# controller.net
KiCad netlist of a schematic drawn in EAGLE
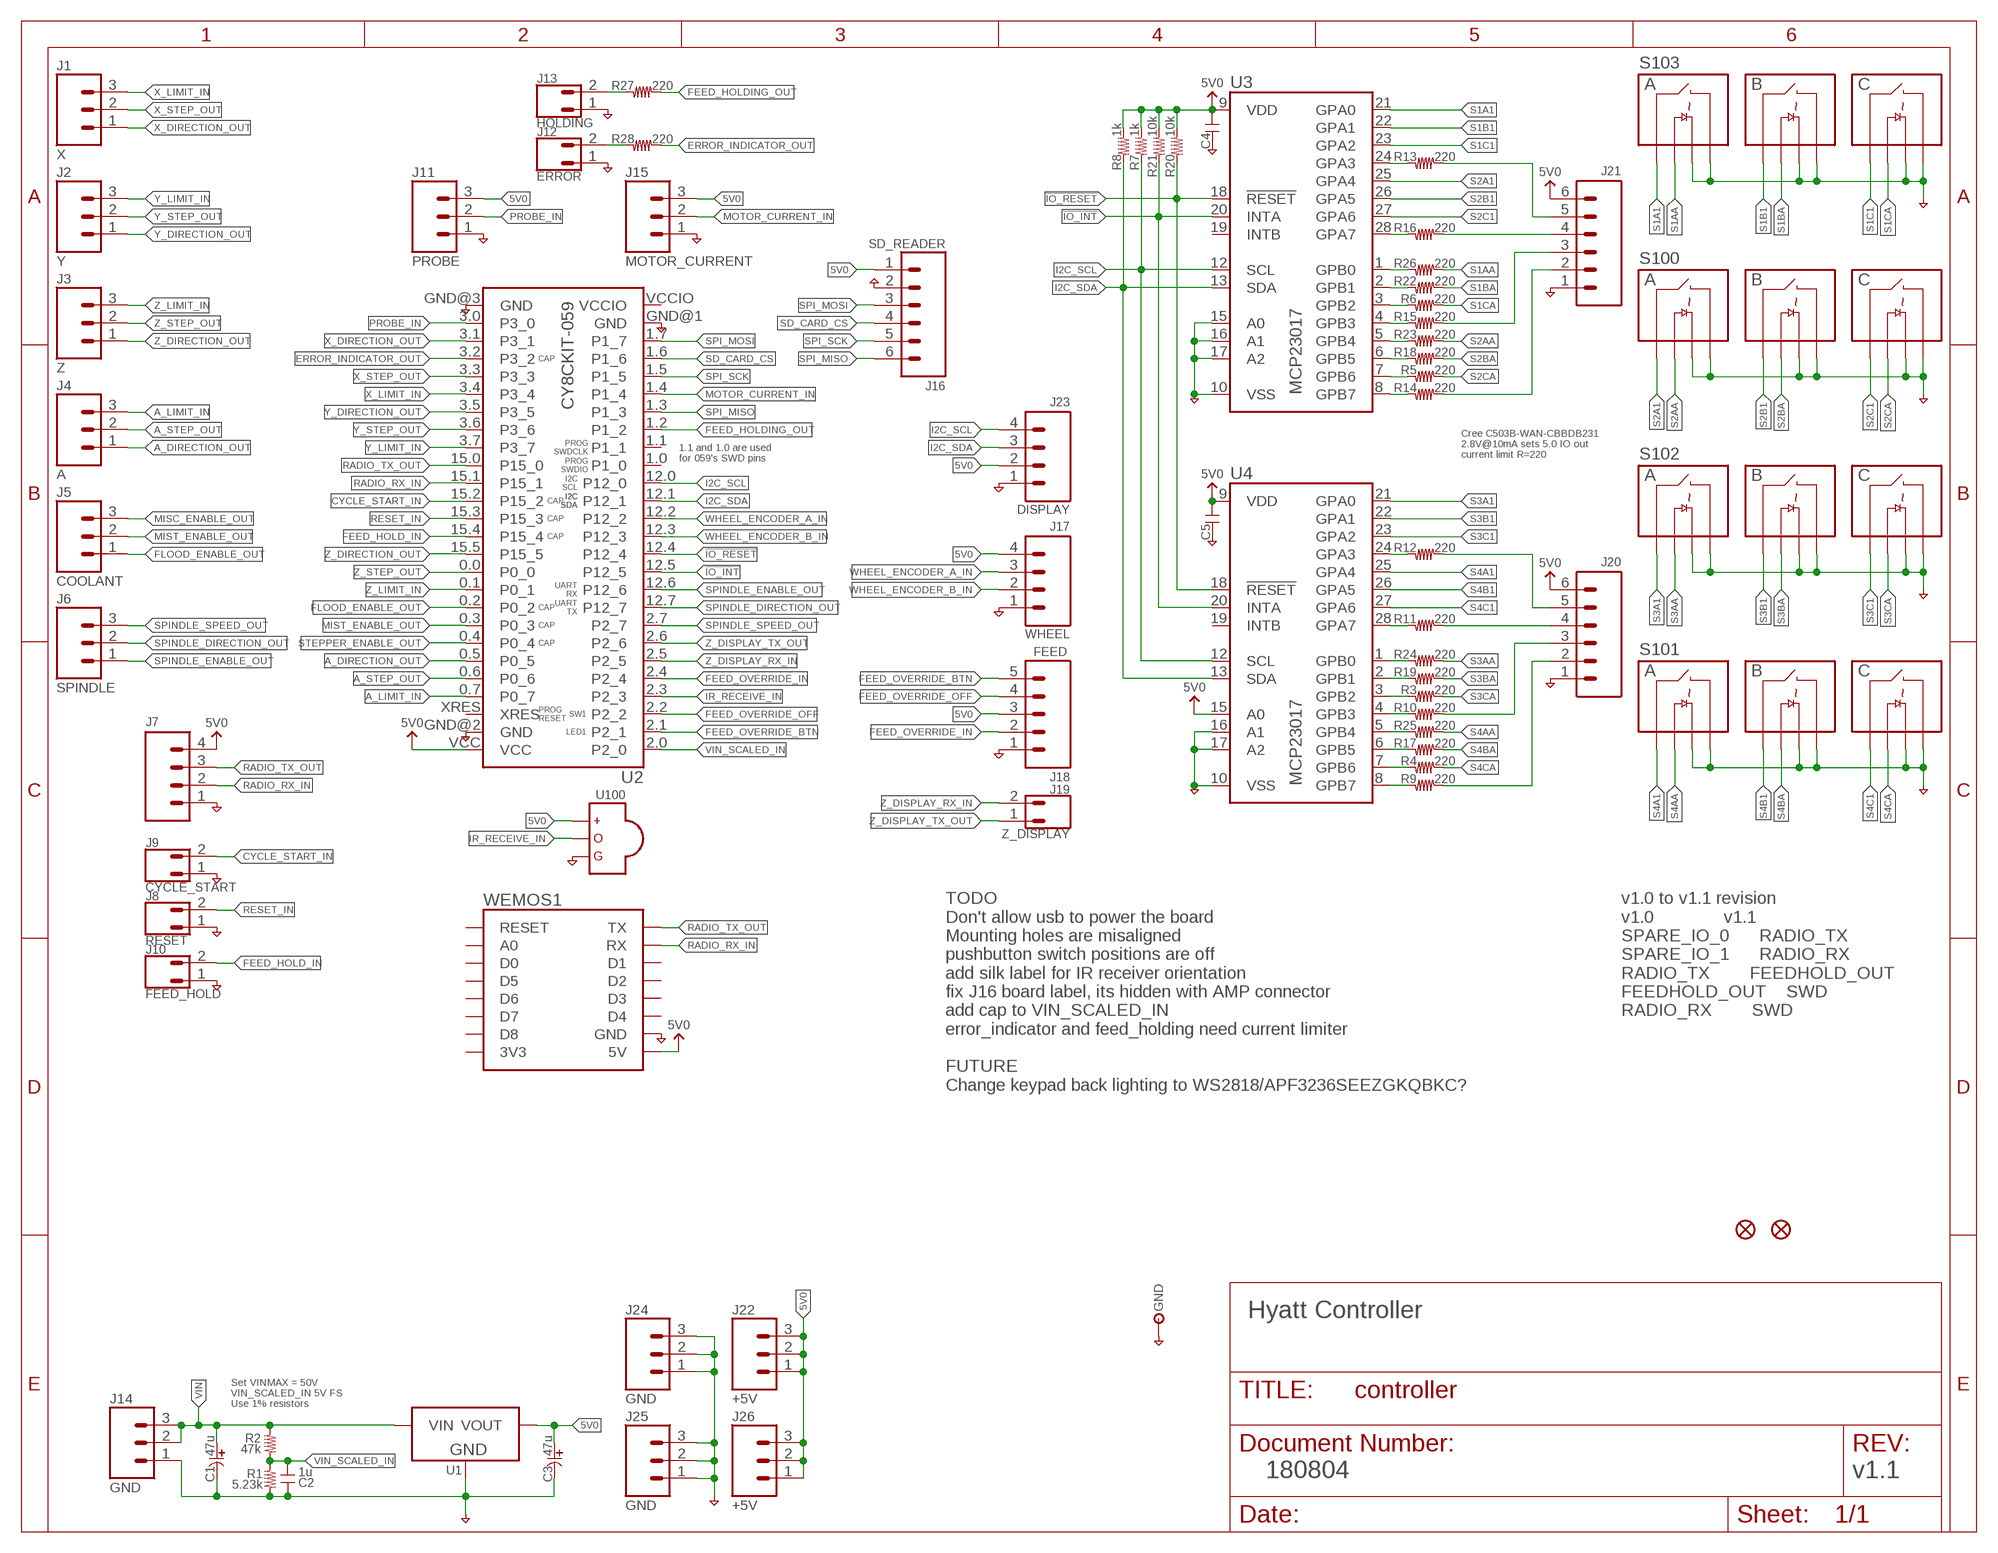
[diagram p0: schematic, sheet 1]

(export (version "E")
  (design (tool "Eeschema 10.0.6"))
  (components
    (comp (ref "C1")
      (value "47u")
      (footprint "eagle-import:E5-10")
      (libsource (lib "eagle-import") (part "C-POLARIZED-E5-10"))
    )
    (comp (ref "C2")
      (value "1u")
      (footprint "eagle-import:C0603")
      (libsource (lib "eagle-import") (part "C-0603"))
    )
    (comp (ref "C3")
      (value "47u")
      (footprint "eagle-import:E5-10")
      (libsource (lib "eagle-import") (part "C-POLARIZED-E5-10"))
    )
    (comp (ref "C4")
      (value "C-0603")
      (footprint "eagle-import:C0603")
      (libsource (lib "eagle-import") (part "C-0603"))
    )
    (comp (ref "C5")
      (value "C-0603")
      (footprint "eagle-import:C0603")
      (libsource (lib "eagle-import") (part "C-0603"))
    )
    (comp (ref "FID1")
      (value "FIDUCIAL1.5X3")
      (footprint "eagle-import:FIDUCIAL-1.5X3")
      (libsource (lib "eagle-import") (part "FIDUCIAL1.5X3"))
    )
    (comp (ref "FID2")
      (value "FIDUCIAL1.5X3")
      (footprint "eagle-import:FIDUCIAL-1.5X3")
      (libsource (lib "eagle-import") (part "FIDUCIAL1.5X3"))
    )
    (comp (ref "GND")
      (value "TESTPOINTTHRU")
      (footprint "eagle-import:TPTHRU")
      (libsource (lib "eagle-import") (part "TESTPOINTTHRU"))
    )
    (comp (ref "J1")
      (value "X")
      (footprint "eagle-import:CONN-3.81MM-KF2EDG-3")
      (libsource (lib "eagle-import") (part "CONN-03-3.81MM-PLUGIN-SCREW"))
    )
    (comp (ref "J2")
      (value "Y")
      (footprint "eagle-import:CONN-3.81MM-KF2EDG-3")
      (libsource (lib "eagle-import") (part "CONN-03-3.81MM-PLUGIN-SCREW"))
    )
    (comp (ref "J3")
      (value "Z")
      (footprint "eagle-import:CONN-3.81MM-KF2EDG-3")
      (libsource (lib "eagle-import") (part "CONN-03-3.81MM-PLUGIN-SCREW"))
    )
    (comp (ref "J4")
      (value "A")
      (footprint "eagle-import:CONN-3.81MM-KF2EDG-3")
      (libsource (lib "eagle-import") (part "CONN-03-3.81MM-PLUGIN-SCREW"))
    )
    (comp (ref "J5")
      (value "COOLANT")
      (footprint "eagle-import:CONN-3.81MM-KF2EDG-3")
      (libsource (lib "eagle-import") (part "CONN-03-3.81MM-PLUGIN-SCREW"))
    )
    (comp (ref "J6")
      (value "SPINDLE")
      (footprint "eagle-import:CONN-3.81MM-KF2EDG-3")
      (libsource (lib "eagle-import") (part "CONN-03-3.81MM-PLUGIN-SCREW"))
    )
    (comp (ref "J7")
      (value "CONN-04-0.1")
      (footprint "eagle-import:1X04")
      (libsource (lib "eagle-import") (part "CONN-04-0.1"))
    )
    (comp (ref "J8")
      (value "RESET")
      (footprint "eagle-import:CONN-.100-2")
      (libsource (lib "eagle-import") (part "CONN-02-.100-VERT-HEADER"))
    )
    (comp (ref "J9")
      (value "CYCLE_START")
      (footprint "eagle-import:CONN-.100-2")
      (libsource (lib "eagle-import") (part "CONN-02-.100-VERT-HEADER"))
    )
    (comp (ref "J10")
      (value "FEED_HOLD")
      (footprint "eagle-import:CONN-.100-2")
      (libsource (lib "eagle-import") (part "CONN-02-.100-VERT-HEADER"))
    )
    (comp (ref "J11")
      (value "PROBE")
      (footprint "eagle-import:CONN-3.81MM-KF2EDG-3")
      (libsource (lib "eagle-import") (part "CONN-03-3.81MM-PLUGIN-SCREW"))
    )
    (comp (ref "J12")
      (value "ERROR")
      (footprint "eagle-import:CONN-.100-2")
      (libsource (lib "eagle-import") (part "CONN-02-.100-VERT-HEADER"))
    )
    (comp (ref "J13")
      (value "HOLDING")
      (footprint "eagle-import:CONN-.100-2")
      (libsource (lib "eagle-import") (part "CONN-02-.100-VERT-HEADER"))
    )
    (comp (ref "J14")
      (value "GND")
      (footprint "eagle-import:CONN-3.81MM-KF2EDG-3")
      (libsource (lib "eagle-import") (part "CONN-03-3.81MM-PLUGIN-SCREW"))
    )
    (comp (ref "J15")
      (value "MOTOR_CURRENT")
      (footprint "eagle-import:CONN-3.81MM-KF2EDG-3")
      (libsource (lib "eagle-import") (part "CONN-03-3.81MM-PLUGIN-SCREW"))
    )
    (comp (ref "J16")
      (value "SD_READER")
      (footprint "eagle-import:1X06")
      (libsource (lib "eagle-import") (part "CONN-06-0.1"))
    )
    (comp (ref "J17")
      (value "WHEEL")
      (footprint "eagle-import:CONN-.100-4")
      (libsource (lib "eagle-import") (part "CONN-04-.100-VERT-HEADER"))
    )
    (comp (ref "J18")
      (value "FEED")
      (footprint "eagle-import:1X05")
      (libsource (lib "eagle-import") (part "CONN-05-PTH"))
    )
    (comp (ref "J19")
      (value "Z_DISPLAY")
      (footprint "eagle-import:CONN-3.81MM-KF2EDG-2")
      (libsource (lib "eagle-import") (part "CONN-02-3.81MM-PLUGIN-SCREW"))
    )
    (comp (ref "J20")
      (value "CONN-06-.100-VERT-HEADER")
      (footprint "eagle-import:CONN-.100-6")
      (libsource (lib "eagle-import") (part "CONN-06-.100-VERT-HEADER"))
    )
    (comp (ref "J21")
      (value "CONN-06-.100-VERT-HEADER")
      (footprint "eagle-import:CONN-.100-6")
      (libsource (lib "eagle-import") (part "CONN-06-.100-VERT-HEADER"))
    )
    (comp (ref "J22")
      (value "+5V")
      (footprint "eagle-import:CONN-3.81MM-KF2EDG-3")
      (libsource (lib "eagle-import") (part "CONN-03-3.81MM-PLUGIN-SCREW"))
    )
    (comp (ref "J23")
      (value "DISPLAY")
      (footprint "eagle-import:CONN-.100-4")
      (libsource (lib "eagle-import") (part "CONN-04-.100-VERT-HEADER"))
    )
    (comp (ref "J24")
      (value "GND")
      (footprint "eagle-import:CONN-3.81MM-KF2EDG-3")
      (libsource (lib "eagle-import") (part "CONN-03-3.81MM-PLUGIN-SCREW"))
    )
    (comp (ref "J25")
      (value "GND")
      (footprint "eagle-import:CONN-3.81MM-KF2EDG-3")
      (libsource (lib "eagle-import") (part "CONN-03-3.81MM-PLUGIN-SCREW"))
    )
    (comp (ref "J26")
      (value "+5V")
      (footprint "eagle-import:CONN-3.81MM-KF2EDG-3")
      (libsource (lib "eagle-import") (part "CONN-03-3.81MM-PLUGIN-SCREW"))
    )
    (comp (ref "R1")
      (value "5.23k")
      (footprint "eagle-import:R0603")
      (libsource (lib "eagle-import") (part "R-0603"))
    )
    (comp (ref "R2")
      (value "47k")
      (footprint "eagle-import:R0603")
      (libsource (lib "eagle-import") (part "R-0603"))
    )
    (comp (ref "R3")
      (value "220")
      (footprint "eagle-import:R0603")
      (libsource (lib "eagle-import") (part "R-0603"))
    )
    (comp (ref "R4")
      (value "220")
      (footprint "eagle-import:R0603")
      (libsource (lib "eagle-import") (part "R-0603"))
    )
    (comp (ref "R5")
      (value "220")
      (footprint "eagle-import:R0603")
      (libsource (lib "eagle-import") (part "R-0603"))
    )
    (comp (ref "R6")
      (value "220")
      (footprint "eagle-import:R0603")
      (libsource (lib "eagle-import") (part "R-0603"))
    )
    (comp (ref "R7")
      (value "1k")
      (footprint "eagle-import:R0603")
      (libsource (lib "eagle-import") (part "R-0603"))
    )
    (comp (ref "R8")
      (value "1k")
      (footprint "eagle-import:R0603")
      (libsource (lib "eagle-import") (part "R-0603"))
    )
    (comp (ref "R9")
      (value "220")
      (footprint "eagle-import:R0603")
      (libsource (lib "eagle-import") (part "R-0603"))
    )
    (comp (ref "R10")
      (value "220")
      (footprint "eagle-import:R0603")
      (libsource (lib "eagle-import") (part "R-0603"))
    )
    (comp (ref "R11")
      (value "220")
      (footprint "eagle-import:R0603")
      (libsource (lib "eagle-import") (part "R-0603"))
    )
    (comp (ref "R12")
      (value "220")
      (footprint "eagle-import:R0603")
      (libsource (lib "eagle-import") (part "R-0603"))
    )
    (comp (ref "R13")
      (value "220")
      (footprint "eagle-import:R0603")
      (libsource (lib "eagle-import") (part "R-0603"))
    )
    (comp (ref "R14")
      (value "220")
      (footprint "eagle-import:R0603")
      (libsource (lib "eagle-import") (part "R-0603"))
    )
    (comp (ref "R15")
      (value "220")
      (footprint "eagle-import:R0603")
      (libsource (lib "eagle-import") (part "R-0603"))
    )
    (comp (ref "R16")
      (value "220")
      (footprint "eagle-import:R0603")
      (libsource (lib "eagle-import") (part "R-0603"))
    )
    (comp (ref "R17")
      (value "220")
      (footprint "eagle-import:R0603")
      (libsource (lib "eagle-import") (part "R-0603"))
    )
    (comp (ref "R18")
      (value "220")
      (footprint "eagle-import:R0603")
      (libsource (lib "eagle-import") (part "R-0603"))
    )
    (comp (ref "R19")
      (value "220")
      (footprint "eagle-import:R0603")
      (libsource (lib "eagle-import") (part "R-0603"))
    )
    (comp (ref "R20")
      (value "10k")
      (footprint "eagle-import:R0603")
      (libsource (lib "eagle-import") (part "R-0603"))
    )
    (comp (ref "R21")
      (value "10k")
      (footprint "eagle-import:R0603")
      (libsource (lib "eagle-import") (part "R-0603"))
    )
    (comp (ref "R22")
      (value "220")
      (footprint "eagle-import:R0603")
      (libsource (lib "eagle-import") (part "R-0603"))
    )
    (comp (ref "R23")
      (value "220")
      (footprint "eagle-import:R0603")
      (libsource (lib "eagle-import") (part "R-0603"))
    )
    (comp (ref "R24")
      (value "220")
      (footprint "eagle-import:R0603")
      (libsource (lib "eagle-import") (part "R-0603"))
    )
    (comp (ref "R25")
      (value "220")
      (footprint "eagle-import:R0603")
      (libsource (lib "eagle-import") (part "R-0603"))
    )
    (comp (ref "R26")
      (value "220")
      (footprint "eagle-import:R0603")
      (libsource (lib "eagle-import") (part "R-0603"))
    )
    (comp (ref "R27")
      (value "220")
      (footprint "eagle-import:R0603")
      (libsource (lib "eagle-import") (part "R-0603"))
    )
    (comp (ref "R28")
      (value "220")
      (footprint "eagle-import:R0603")
      (libsource (lib "eagle-import") (part "R-0603"))
    )
    (comp (ref "S100")
      (value "SWITCH-DTMF-3-LED")
      (footprint "eagle-import:SWITCH-DTMF-3-LED")
      (libsource (lib "eagle-import") (part "SWITCH-DTMF-3-LED"))
    )
    (comp (ref "S101")
      (value "SWITCH-DTMF-3-LED")
      (footprint "eagle-import:SWITCH-DTMF-3-LED")
      (libsource (lib "eagle-import") (part "SWITCH-DTMF-3-LED"))
    )
    (comp (ref "S102")
      (value "SWITCH-DTMF-3-LED")
      (footprint "eagle-import:SWITCH-DTMF-3-LED")
      (libsource (lib "eagle-import") (part "SWITCH-DTMF-3-LED"))
    )
    (comp (ref "S103")
      (value "SWITCH-DTMF-3-LED")
      (footprint "eagle-import:SWITCH-DTMF-3-LED")
      (libsource (lib "eagle-import") (part "SWITCH-DTMF-3-LED"))
    )
    (comp (ref "U1")
      (value "VREG-SIP3")
      (footprint "eagle-import:VREG-SIP3")
      (libsource (lib "eagle-import") (part "VREG-SIP3"))
    )
    (comp (ref "U2")
      (value "BOARD-PSOC-CY8CKIT-059")
      (footprint "eagle-import:BOARD-PSOC-CY8CKIT-059")
      (libsource (lib "eagle-import") (part "BOARD-PSOC-CY8CKIT-059"))
    )
    (comp (ref "U3")
      (value "MCP23017")
      (footprint "eagle-import:SO28W")
      (fields (field (name "MF") "MICROCHIP") (field (name "MPN") "MCP23017-E/SO"))
      (libsource (lib "eagle-import") (part "IO-MCP23017SO"))
    )
    (comp (ref "U4")
      (value "MCP23017")
      (footprint "eagle-import:SO28W")
      (fields (field (name "MF") "MICROCHIP") (field (name "MPN") "MCP23017-E/SO"))
      (libsource (lib "eagle-import") (part "IO-MCP23017SO"))
    )
    (comp (ref "U100")
      (value "SENSOR-IR-THRU")
      (footprint "eagle-import:IRDETECTOR-THRU")
      (libsource (lib "eagle-import") (part "SENSOR-IR-THRU"))
    )
    (comp (ref "WEMOS1")
      (value "RADIO-WEMOS-D1-MINI")
      (footprint "eagle-import:WEMOS-D1-MINI")
      (libsource (lib "eagle-import") (part "RADIO-WEMOS-D1-MINI"))
    )
  )
  (nets
    (net (code "1") (name "/~{IO_INT}") (class "Default")
      (node (ref "R21") (pin "1") (pinfunction "1_1") (pintype "passive"))
      (node (ref "U2") (pin "12.5") (pinfunction "P12_5_12.5") (pintype "bidirectional"))
      (node (ref "U3") (pin "20") (pinfunction "INTA_20") (pintype "output"))
      (node (ref "U4") (pin "20") (pinfunction "INTA_20") (pintype "output"))
    )
    (net (code "2") (name "/~{IO_RESET}") (class "Default")
      (node (ref "R20") (pin "1") (pinfunction "1_1") (pintype "passive"))
      (node (ref "U2") (pin "12.4") (pinfunction "P12_4_12.4") (pintype "bidirectional"))
      (node (ref "U3") (pin "18") (pinfunction "~{RESET}_18") (pintype "input"))
      (node (ref "U4") (pin "18") (pinfunction "~{RESET}_18") (pintype "input"))
    )
    (net (code "3") (name "5V0") (class "Default")
      (node (ref "C3") (pin "+") (pinfunction "+_+") (pintype "passive"))
      (node (ref "C4") (pin "1") (pinfunction "1_1") (pintype "passive"))
      (node (ref "C5") (pin "1") (pinfunction "1_1") (pintype "passive"))
      (node (ref "J11") (pin "3") (pinfunction "3_3") (pintype "passive"))
      (node (ref "J15") (pin "3") (pinfunction "3_3") (pintype "passive"))
      (node (ref "J16") (pin "1") (pinfunction "1_1") (pintype "passive"))
      (node (ref "J17") (pin "4") (pinfunction "4_4") (pintype "passive"))
      (node (ref "J18") (pin "3") (pinfunction "3_3") (pintype "passive"))
      (node (ref "J20") (pin "6") (pinfunction "6_6") (pintype "passive"))
      (node (ref "J21") (pin "6") (pinfunction "6_6") (pintype "passive"))
      (node (ref "J22") (pin "1") (pinfunction "1_1") (pintype "passive"))
      (node (ref "J22") (pin "2") (pinfunction "2_2") (pintype "passive"))
      (node (ref "J22") (pin "3") (pinfunction "3_3") (pintype "passive"))
      (node (ref "J23") (pin "2") (pinfunction "2_2") (pintype "passive"))
      (node (ref "J26") (pin "1") (pinfunction "1_1") (pintype "passive"))
      (node (ref "J26") (pin "2") (pinfunction "2_2") (pintype "passive"))
      (node (ref "J26") (pin "3") (pinfunction "3_3") (pintype "passive"))
      (node (ref "J7") (pin "4") (pinfunction "4_4") (pintype "passive"))
      (node (ref "R20") (pin "2") (pinfunction "2_2") (pintype "passive"))
      (node (ref "R21") (pin "2") (pinfunction "2_2") (pintype "passive"))
      (node (ref "R7") (pin "2") (pinfunction "2_2") (pintype "passive"))
      (node (ref "R8") (pin "2") (pinfunction "2_2") (pintype "passive"))
      (node (ref "U1") (pin "3") (pinfunction "VOUT_3") (pintype "bidirectional"))
      (node (ref "U100") (pin "VCC") (pinfunction "VCC_VCC") (pintype "bidirectional"))
      (node (ref "U2") (pin "VCC") (pinfunction "VCC_VCC") (pintype "bidirectional"))
      (node (ref "U3") (pin "9") (pinfunction "VDD_9") (pintype "power_in"))
      (node (ref "U4") (pin "15") (pinfunction "A0_15") (pintype "input"))
      (node (ref "U4") (pin "9") (pinfunction "VDD_9") (pintype "power_in"))
      (node (ref "WEMOS1") (pin "5V") (pinfunction "5V_5V") (pintype "bidirectional"))
    )
    (net (code "4") (name "A_DIRECTION_OUT") (class "Default")
      (node (ref "J4") (pin "1") (pinfunction "1_1") (pintype "passive"))
      (node (ref "U2") (pin "0.5") (pinfunction "P0_5_0.5") (pintype "bidirectional"))
    )
    (net (code "5") (name "A_LIMIT_IN") (class "Default")
      (node (ref "J4") (pin "3") (pinfunction "3_3") (pintype "passive"))
      (node (ref "U2") (pin "0.7") (pinfunction "P0_7_0.7") (pintype "bidirectional"))
    )
    (net (code "6") (name "A_STEP_OUT") (class "Default")
      (node (ref "J4") (pin "2") (pinfunction "2_2") (pintype "passive"))
      (node (ref "U2") (pin "0.6") (pinfunction "P0_6_0.6") (pintype "bidirectional"))
    )
    (net (code "7") (name "CYCLE_START_IN") (class "Default")
      (node (ref "J9") (pin "2") (pinfunction "2_2") (pintype "passive"))
      (node (ref "U2") (pin "15.2") (pinfunction "P15_2_15.2") (pintype "bidirectional"))
    )
    (net (code "8") (name "ERROR_INDICATOR_OUT") (class "Default")
      (node (ref "R28") (pin "2") (pinfunction "2_2") (pintype "passive"))
      (node (ref "U2") (pin "3.2") (pinfunction "P3_2_3.2") (pintype "bidirectional"))
    )
    (net (code "9") (name "FEED_HOLDING_OUT") (class "Default")
      (node (ref "R27") (pin "2") (pinfunction "2_2") (pintype "passive"))
      (node (ref "U2") (pin "1.2") (pinfunction "P1_2_1.2") (pintype "bidirectional"))
    )
    (net (code "10") (name "FEED_HOLD_IN") (class "Default")
      (node (ref "J10") (pin "2") (pinfunction "2_2") (pintype "passive"))
      (node (ref "U2") (pin "15.4") (pinfunction "P15_4_15.4") (pintype "bidirectional"))
    )
    (net (code "11") (name "FEED_OVERRIDE_BTN") (class "Default")
      (node (ref "J18") (pin "5") (pinfunction "5_5") (pintype "passive"))
      (node (ref "U2") (pin "2.1") (pinfunction "P2_1_2.1") (pintype "bidirectional"))
    )
    (net (code "12") (name "FEED_OVERRIDE_IN") (class "Default")
      (node (ref "J18") (pin "2") (pinfunction "2_2") (pintype "passive"))
      (node (ref "U2") (pin "2.4") (pinfunction "P2_4_2.4") (pintype "bidirectional"))
    )
    (net (code "13") (name "FEED_OVERRIDE_OFF") (class "Default")
      (node (ref "J18") (pin "4") (pinfunction "4_4") (pintype "passive"))
      (node (ref "U2") (pin "2.2") (pinfunction "P2_2_2.2") (pintype "bidirectional"))
    )
    (net (code "14") (name "FLOOD_ENABLE_OUT") (class "Default")
      (node (ref "J5") (pin "1") (pinfunction "1_1") (pintype "passive"))
      (node (ref "U2") (pin "0.2") (pinfunction "P0_2_0.2") (pintype "bidirectional"))
    )
    (net (code "15") (name "GND") (class "Default")
      (node (ref "C1") (pin "-") (pinfunction "-_-") (pintype "passive"))
      (node (ref "C2") (pin "2") (pinfunction "2_2") (pintype "passive"))
      (node (ref "C3") (pin "-") (pinfunction "-_-") (pintype "passive"))
      (node (ref "C4") (pin "2") (pinfunction "2_2") (pintype "passive"))
      (node (ref "C5") (pin "2") (pinfunction "2_2") (pintype "passive"))
      (node (ref "GND") (pin "1") (pinfunction "P$1_1") (pintype "bidirectional"))
      (node (ref "J10") (pin "1") (pinfunction "1_1") (pintype "passive"))
      (node (ref "J11") (pin "1") (pinfunction "1_1") (pintype "passive"))
      (node (ref "J12") (pin "1") (pinfunction "1_1") (pintype "passive"))
      (node (ref "J13") (pin "1") (pinfunction "1_1") (pintype "passive"))
      (node (ref "J14") (pin "1") (pinfunction "1_1") (pintype "passive"))
      (node (ref "J15") (pin "1") (pinfunction "1_1") (pintype "passive"))
      (node (ref "J16") (pin "2") (pinfunction "2_2") (pintype "passive"))
      (node (ref "J17") (pin "1") (pinfunction "1_1") (pintype "passive"))
      (node (ref "J18") (pin "1") (pinfunction "1_1") (pintype "passive"))
      (node (ref "J20") (pin "1") (pinfunction "1_1") (pintype "passive"))
      (node (ref "J21") (pin "1") (pinfunction "1_1") (pintype "passive"))
      (node (ref "J23") (pin "1") (pinfunction "1_1") (pintype "passive"))
      (node (ref "J24") (pin "1") (pinfunction "1_1") (pintype "passive"))
      (node (ref "J24") (pin "2") (pinfunction "2_2") (pintype "passive"))
      (node (ref "J24") (pin "3") (pinfunction "3_3") (pintype "passive"))
      (node (ref "J25") (pin "1") (pinfunction "1_1") (pintype "passive"))
      (node (ref "J25") (pin "2") (pinfunction "2_2") (pintype "passive"))
      (node (ref "J25") (pin "3") (pinfunction "3_3") (pintype "passive"))
      (node (ref "J7") (pin "1") (pinfunction "1_1") (pintype "passive"))
      (node (ref "J8") (pin "1") (pinfunction "1_1") (pintype "passive"))
      (node (ref "J9") (pin "1") (pinfunction "1_1") (pintype "passive"))
      (node (ref "R1") (pin "1") (pinfunction "1_1") (pintype "passive"))
      (node (ref "S100") (pin "A_2") (pinfunction "A_2_A_2") (pintype "bidirectional"))
      (node (ref "S100") (pin "A_C") (pinfunction "A_C_A_C") (pintype "bidirectional"))
      (node (ref "S100") (pin "B_2") (pinfunction "B_2_B_2") (pintype "bidirectional"))
      (node (ref "S100") (pin "B_C") (pinfunction "B_C_B_C") (pintype "bidirectional"))
      (node (ref "S100") (pin "C_2") (pinfunction "C_2_C_2") (pintype "bidirectional"))
      (node (ref "S100") (pin "C_C") (pinfunction "C_C_C_C") (pintype "bidirectional"))
      (node (ref "S101") (pin "A_2") (pinfunction "A_2_A_2") (pintype "bidirectional"))
      (node (ref "S101") (pin "A_C") (pinfunction "A_C_A_C") (pintype "bidirectional"))
      (node (ref "S101") (pin "B_2") (pinfunction "B_2_B_2") (pintype "bidirectional"))
      (node (ref "S101") (pin "B_C") (pinfunction "B_C_B_C") (pintype "bidirectional"))
      (node (ref "S101") (pin "C_2") (pinfunction "C_2_C_2") (pintype "bidirectional"))
      (node (ref "S101") (pin "C_C") (pinfunction "C_C_C_C") (pintype "bidirectional"))
      (node (ref "S102") (pin "A_2") (pinfunction "A_2_A_2") (pintype "bidirectional"))
      (node (ref "S102") (pin "A_C") (pinfunction "A_C_A_C") (pintype "bidirectional"))
      (node (ref "S102") (pin "B_2") (pinfunction "B_2_B_2") (pintype "bidirectional"))
      (node (ref "S102") (pin "B_C") (pinfunction "B_C_B_C") (pintype "bidirectional"))
      (node (ref "S102") (pin "C_2") (pinfunction "C_2_C_2") (pintype "bidirectional"))
      (node (ref "S102") (pin "C_C") (pinfunction "C_C_C_C") (pintype "bidirectional"))
      (node (ref "S103") (pin "A_2") (pinfunction "A_2_A_2") (pintype "bidirectional"))
      (node (ref "S103") (pin "A_C") (pinfunction "A_C_A_C") (pintype "bidirectional"))
      (node (ref "S103") (pin "B_2") (pinfunction "B_2_B_2") (pintype "bidirectional"))
      (node (ref "S103") (pin "B_C") (pinfunction "B_C_B_C") (pintype "bidirectional"))
      (node (ref "S103") (pin "C_2") (pinfunction "C_2_C_2") (pintype "bidirectional"))
      (node (ref "S103") (pin "C_C") (pinfunction "C_C_C_C") (pintype "bidirectional"))
      (node (ref "U1") (pin "2") (pinfunction "GND_2") (pintype "bidirectional"))
      (node (ref "U100") (pin "GND") (pinfunction "GND_GND") (pintype "bidirectional"))
      (node (ref "U2") (pin "GND@1") (pinfunction "GND_GND@1") (pintype "bidirectional"))
      (node (ref "U2") (pin "GND@2") (pinfunction "GND_GND@2") (pintype "bidirectional"))
      (node (ref "U2") (pin "GND@3") (pinfunction "GND_GND@3") (pintype "bidirectional"))
      (node (ref "U3") (pin "10") (pinfunction "VSS_10") (pintype "power_in"))
      (node (ref "U3") (pin "15") (pinfunction "A0_15") (pintype "input"))
      (node (ref "U3") (pin "16") (pinfunction "A1_16") (pintype "input"))
      (node (ref "U3") (pin "17") (pinfunction "A2_17") (pintype "input"))
      (node (ref "U4") (pin "10") (pinfunction "VSS_10") (pintype "power_in"))
      (node (ref "U4") (pin "16") (pinfunction "A1_16") (pintype "input"))
      (node (ref "U4") (pin "17") (pinfunction "A2_17") (pintype "input"))
      (node (ref "WEMOS1") (pin "GND") (pinfunction "GND_GND") (pintype "bidirectional"))
    )
    (net (code "16") (name "I2C_SCL") (class "Default")
      (node (ref "J23") (pin "4") (pinfunction "4_4") (pintype "passive"))
      (node (ref "R7") (pin "1") (pinfunction "1_1") (pintype "passive"))
      (node (ref "U2") (pin "12.0") (pinfunction "P12_0_12.0") (pintype "bidirectional"))
      (node (ref "U3") (pin "12") (pinfunction "SCL_12") (pintype "input"))
      (node (ref "U4") (pin "12") (pinfunction "SCL_12") (pintype "input"))
    )
    (net (code "17") (name "I2C_SDA") (class "Default")
      (node (ref "J23") (pin "3") (pinfunction "3_3") (pintype "passive"))
      (node (ref "R8") (pin "1") (pinfunction "1_1") (pintype "passive"))
      (node (ref "U2") (pin "12.1") (pinfunction "P12_1_12.1") (pintype "bidirectional"))
      (node (ref "U3") (pin "13") (pinfunction "SDA_13") (pintype "bidirectional"))
      (node (ref "U4") (pin "13") (pinfunction "SDA_13") (pintype "bidirectional"))
    )
    (net (code "18") (name "IR_RECEIVE_IN") (class "Default")
      (node (ref "U100") (pin "VOUT") (pinfunction "VOUT_VOUT") (pintype "bidirectional"))
      (node (ref "U2") (pin "2.3") (pinfunction "P2_3_2.3") (pintype "bidirectional"))
    )
    (net (code "19") (name "MISC_ENABLE_OUT") (class "Default")
      (node (ref "J5") (pin "3") (pinfunction "3_3") (pintype "passive"))
    )
    (net (code "20") (name "MIST_ENABLE_OUT") (class "Default")
      (node (ref "J5") (pin "2") (pinfunction "2_2") (pintype "passive"))
      (node (ref "U2") (pin "0.3") (pinfunction "P0_3_0.3") (pintype "bidirectional"))
    )
    (net (code "21") (name "MOTOR_CURRENT_IN") (class "Default")
      (node (ref "J15") (pin "2") (pinfunction "2_2") (pintype "passive"))
      (node (ref "U2") (pin "1.4") (pinfunction "P1_4_1.4") (pintype "bidirectional"))
    )
    (net (code "22") (name "Net-(J12-Pad2)") (class "Default")
      (node (ref "J12") (pin "2") (pinfunction "2_2") (pintype "passive"))
      (node (ref "R28") (pin "1") (pinfunction "1_1") (pintype "passive"))
    )
    (net (code "23") (name "Net-(J13-Pad2)") (class "Default")
      (node (ref "J13") (pin "2") (pinfunction "2_2") (pintype "passive"))
      (node (ref "R27") (pin "1") (pinfunction "1_1") (pintype "passive"))
    )
    (net (code "24") (name "Net-(J20-Pad2)") (class "Default")
      (node (ref "J20") (pin "2") (pinfunction "2_2") (pintype "passive"))
      (node (ref "R9") (pin "2") (pinfunction "2_2") (pintype "passive"))
    )
    (net (code "25") (name "Net-(J20-Pad3)") (class "Default")
      (node (ref "J20") (pin "3") (pinfunction "3_3") (pintype "passive"))
      (node (ref "R10") (pin "2") (pinfunction "2_2") (pintype "passive"))
    )
    (net (code "26") (name "Net-(J20-Pad4)") (class "Default")
      (node (ref "J20") (pin "4") (pinfunction "4_4") (pintype "passive"))
      (node (ref "R11") (pin "2") (pinfunction "2_2") (pintype "passive"))
    )
    (net (code "27") (name "Net-(J20-Pad5)") (class "Default")
      (node (ref "J20") (pin "5") (pinfunction "5_5") (pintype "passive"))
      (node (ref "R12") (pin "2") (pinfunction "2_2") (pintype "passive"))
    )
    (net (code "28") (name "Net-(J21-Pad2)") (class "Default")
      (node (ref "J21") (pin "2") (pinfunction "2_2") (pintype "passive"))
      (node (ref "R14") (pin "2") (pinfunction "2_2") (pintype "passive"))
    )
    (net (code "29") (name "Net-(J21-Pad3)") (class "Default")
      (node (ref "J21") (pin "3") (pinfunction "3_3") (pintype "passive"))
      (node (ref "R15") (pin "2") (pinfunction "2_2") (pintype "passive"))
    )
    (net (code "30") (name "Net-(J21-Pad4)") (class "Default")
      (node (ref "J21") (pin "4") (pinfunction "4_4") (pintype "passive"))
      (node (ref "R16") (pin "2") (pinfunction "2_2") (pintype "passive"))
    )
    (net (code "31") (name "Net-(J21-Pad5)") (class "Default")
      (node (ref "J21") (pin "5") (pinfunction "5_5") (pintype "passive"))
      (node (ref "R13") (pin "2") (pinfunction "2_2") (pintype "passive"))
    )
    (net (code "32") (name "Net-(U3-GPA3)") (class "Default")
      (node (ref "R13") (pin "1") (pinfunction "1_1") (pintype "passive"))
      (node (ref "U3") (pin "24") (pinfunction "GPA3_24") (pintype "bidirectional"))
    )
    (net (code "33") (name "Net-(U3-GPA7)") (class "Default")
      (node (ref "R16") (pin "1") (pinfunction "1_1") (pintype "passive"))
      (node (ref "U3") (pin "28") (pinfunction "GPA7_28") (pintype "bidirectional"))
    )
    (net (code "34") (name "Net-(U3-GPB0)") (class "Default")
      (node (ref "R26") (pin "1") (pinfunction "1_1") (pintype "passive"))
      (node (ref "U3") (pin "1") (pinfunction "GPB0_1") (pintype "bidirectional"))
    )
    (net (code "35") (name "Net-(U3-GPB1)") (class "Default")
      (node (ref "R22") (pin "1") (pinfunction "1_1") (pintype "passive"))
      (node (ref "U3") (pin "2") (pinfunction "GPB1_2") (pintype "bidirectional"))
    )
    (net (code "36") (name "Net-(U3-GPB2)") (class "Default")
      (node (ref "R6") (pin "1") (pinfunction "1_1") (pintype "passive"))
      (node (ref "U3") (pin "3") (pinfunction "GPB2_3") (pintype "bidirectional"))
    )
    (net (code "37") (name "Net-(U3-GPB3)") (class "Default")
      (node (ref "R15") (pin "1") (pinfunction "1_1") (pintype "passive"))
      (node (ref "U3") (pin "4") (pinfunction "GPB3_4") (pintype "bidirectional"))
    )
    (net (code "38") (name "Net-(U3-GPB4)") (class "Default")
      (node (ref "R23") (pin "1") (pinfunction "1_1") (pintype "passive"))
      (node (ref "U3") (pin "5") (pinfunction "GPB4_5") (pintype "bidirectional"))
    )
    (net (code "39") (name "Net-(U3-GPB5)") (class "Default")
      (node (ref "R18") (pin "1") (pinfunction "1_1") (pintype "passive"))
      (node (ref "U3") (pin "6") (pinfunction "GPB5_6") (pintype "bidirectional"))
    )
    (net (code "40") (name "Net-(U3-GPB6)") (class "Default")
      (node (ref "R5") (pin "1") (pinfunction "1_1") (pintype "passive"))
      (node (ref "U3") (pin "7") (pinfunction "GPB6_7") (pintype "bidirectional"))
    )
    (net (code "41") (name "Net-(U3-GPB7)") (class "Default")
      (node (ref "R14") (pin "1") (pinfunction "1_1") (pintype "passive"))
      (node (ref "U3") (pin "8") (pinfunction "GPB7_8") (pintype "bidirectional"))
    )
    (net (code "42") (name "Net-(U4-GPA3)") (class "Default")
      (node (ref "R12") (pin "1") (pinfunction "1_1") (pintype "passive"))
      (node (ref "U4") (pin "24") (pinfunction "GPA3_24") (pintype "bidirectional"))
    )
    (net (code "43") (name "Net-(U4-GPA7)") (class "Default")
      (node (ref "R11") (pin "1") (pinfunction "1_1") (pintype "passive"))
      (node (ref "U4") (pin "28") (pinfunction "GPA7_28") (pintype "bidirectional"))
    )
    (net (code "44") (name "Net-(U4-GPB0)") (class "Default")
      (node (ref "R24") (pin "1") (pinfunction "1_1") (pintype "passive"))
      (node (ref "U4") (pin "1") (pinfunction "GPB0_1") (pintype "bidirectional"))
    )
    (net (code "45") (name "Net-(U4-GPB1)") (class "Default")
      (node (ref "R19") (pin "1") (pinfunction "1_1") (pintype "passive"))
      (node (ref "U4") (pin "2") (pinfunction "GPB1_2") (pintype "bidirectional"))
    )
    (net (code "46") (name "Net-(U4-GPB2)") (class "Default")
      (node (ref "R3") (pin "1") (pinfunction "1_1") (pintype "passive"))
      (node (ref "U4") (pin "3") (pinfunction "GPB2_3") (pintype "bidirectional"))
    )
    (net (code "47") (name "Net-(U4-GPB3)") (class "Default")
      (node (ref "R10") (pin "1") (pinfunction "1_1") (pintype "passive"))
      (node (ref "U4") (pin "4") (pinfunction "GPB3_4") (pintype "bidirectional"))
    )
    (net (code "48") (name "Net-(U4-GPB4)") (class "Default")
      (node (ref "R25") (pin "1") (pinfunction "1_1") (pintype "passive"))
      (node (ref "U4") (pin "5") (pinfunction "GPB4_5") (pintype "bidirectional"))
    )
    (net (code "49") (name "Net-(U4-GPB5)") (class "Default")
      (node (ref "R17") (pin "1") (pinfunction "1_1") (pintype "passive"))
      (node (ref "U4") (pin "6") (pinfunction "GPB5_6") (pintype "bidirectional"))
    )
    (net (code "50") (name "Net-(U4-GPB6)") (class "Default")
      (node (ref "R4") (pin "1") (pinfunction "1_1") (pintype "passive"))
      (node (ref "U4") (pin "7") (pinfunction "GPB6_7") (pintype "bidirectional"))
    )
    (net (code "51") (name "Net-(U4-GPB7)") (class "Default")
      (node (ref "R9") (pin "1") (pinfunction "1_1") (pintype "passive"))
      (node (ref "U4") (pin "8") (pinfunction "GPB7_8") (pintype "bidirectional"))
    )
    (net (code "52") (name "PROBE_IN") (class "Default")
      (node (ref "J11") (pin "2") (pinfunction "2_2") (pintype "passive"))
      (node (ref "U2") (pin "3.0") (pinfunction "P3_0_3.0") (pintype "bidirectional"))
    )
    (net (code "53") (name "RADIO_RX_IN") (class "Default")
      (node (ref "J7") (pin "2") (pinfunction "2_2") (pintype "passive"))
      (node (ref "U2") (pin "15.1") (pinfunction "P15_1_15.1") (pintype "bidirectional"))
      (node (ref "WEMOS1") (pin "RX") (pinfunction "RX_RX") (pintype "bidirectional"))
    )
    (net (code "54") (name "RADIO_TX_OUT") (class "Default")
      (node (ref "J7") (pin "3") (pinfunction "3_3") (pintype "passive"))
      (node (ref "U2") (pin "15.0") (pinfunction "P15_0_15.0") (pintype "bidirectional"))
      (node (ref "WEMOS1") (pin "TX") (pinfunction "TX_TX") (pintype "bidirectional"))
    )
    (net (code "55") (name "RESET_IN") (class "Default")
      (node (ref "J8") (pin "2") (pinfunction "2_2") (pintype "passive"))
      (node (ref "U2") (pin "15.3") (pinfunction "P15_3_15.3") (pintype "bidirectional"))
    )
    (net (code "56") (name "S1A1") (class "Default")
      (node (ref "S103") (pin "A_1") (pinfunction "A_1_A_1") (pintype "bidirectional"))
      (node (ref "U3") (pin "21") (pinfunction "GPA0_21") (pintype "bidirectional"))
    )
    (net (code "57") (name "S1AA") (class "Default")
      (node (ref "R26") (pin "2") (pinfunction "2_2") (pintype "passive"))
      (node (ref "S103") (pin "A_A") (pinfunction "A_A_A_A") (pintype "bidirectional"))
    )
    (net (code "58") (name "S1B1") (class "Default")
      (node (ref "S103") (pin "B_1") (pinfunction "B_1_B_1") (pintype "bidirectional"))
      (node (ref "U3") (pin "22") (pinfunction "GPA1_22") (pintype "bidirectional"))
    )
    (net (code "59") (name "S1BA") (class "Default")
      (node (ref "R22") (pin "2") (pinfunction "2_2") (pintype "passive"))
      (node (ref "S103") (pin "B_A") (pinfunction "B_A_B_A") (pintype "bidirectional"))
    )
    (net (code "60") (name "S1C1") (class "Default")
      (node (ref "S103") (pin "C_1") (pinfunction "C_1_C_1") (pintype "bidirectional"))
      (node (ref "U3") (pin "23") (pinfunction "GPA2_23") (pintype "bidirectional"))
    )
    (net (code "61") (name "S1CA") (class "Default")
      (node (ref "R6") (pin "2") (pinfunction "2_2") (pintype "passive"))
      (node (ref "S103") (pin "C_A") (pinfunction "C_A_C_A") (pintype "bidirectional"))
    )
    (net (code "62") (name "S2A1") (class "Default")
      (node (ref "S100") (pin "A_1") (pinfunction "A_1_A_1") (pintype "bidirectional"))
      (node (ref "U3") (pin "25") (pinfunction "GPA4_25") (pintype "bidirectional"))
    )
    (net (code "63") (name "S2AA") (class "Default")
      (node (ref "R23") (pin "2") (pinfunction "2_2") (pintype "passive"))
      (node (ref "S100") (pin "A_A") (pinfunction "A_A_A_A") (pintype "bidirectional"))
    )
    (net (code "64") (name "S2B1") (class "Default")
      (node (ref "S100") (pin "B_1") (pinfunction "B_1_B_1") (pintype "bidirectional"))
      (node (ref "U3") (pin "26") (pinfunction "GPA5_26") (pintype "bidirectional"))
    )
    (net (code "65") (name "S2BA") (class "Default")
      (node (ref "R18") (pin "2") (pinfunction "2_2") (pintype "passive"))
      (node (ref "S100") (pin "B_A") (pinfunction "B_A_B_A") (pintype "bidirectional"))
    )
    (net (code "66") (name "S2C1") (class "Default")
      (node (ref "S100") (pin "C_1") (pinfunction "C_1_C_1") (pintype "bidirectional"))
      (node (ref "U3") (pin "27") (pinfunction "GPA6_27") (pintype "bidirectional"))
    )
    (net (code "67") (name "S2CA") (class "Default")
      (node (ref "R5") (pin "2") (pinfunction "2_2") (pintype "passive"))
      (node (ref "S100") (pin "C_A") (pinfunction "C_A_C_A") (pintype "bidirectional"))
    )
    (net (code "68") (name "S3A1") (class "Default")
      (node (ref "S102") (pin "A_1") (pinfunction "A_1_A_1") (pintype "bidirectional"))
      (node (ref "U4") (pin "21") (pinfunction "GPA0_21") (pintype "bidirectional"))
    )
    (net (code "69") (name "S3AA") (class "Default")
      (node (ref "R24") (pin "2") (pinfunction "2_2") (pintype "passive"))
      (node (ref "S102") (pin "A_A") (pinfunction "A_A_A_A") (pintype "bidirectional"))
    )
    (net (code "70") (name "S3B1") (class "Default")
      (node (ref "S102") (pin "B_1") (pinfunction "B_1_B_1") (pintype "bidirectional"))
      (node (ref "U4") (pin "22") (pinfunction "GPA1_22") (pintype "bidirectional"))
    )
    (net (code "71") (name "S3BA") (class "Default")
      (node (ref "R19") (pin "2") (pinfunction "2_2") (pintype "passive"))
      (node (ref "S102") (pin "B_A") (pinfunction "B_A_B_A") (pintype "bidirectional"))
    )
    (net (code "72") (name "S3C1") (class "Default")
      (node (ref "S102") (pin "C_1") (pinfunction "C_1_C_1") (pintype "bidirectional"))
      (node (ref "U4") (pin "23") (pinfunction "GPA2_23") (pintype "bidirectional"))
    )
    (net (code "73") (name "S3CA") (class "Default")
      (node (ref "R3") (pin "2") (pinfunction "2_2") (pintype "passive"))
      (node (ref "S102") (pin "C_A") (pinfunction "C_A_C_A") (pintype "bidirectional"))
    )
    (net (code "74") (name "S4A1") (class "Default")
      (node (ref "S101") (pin "A_1") (pinfunction "A_1_A_1") (pintype "bidirectional"))
      (node (ref "U4") (pin "25") (pinfunction "GPA4_25") (pintype "bidirectional"))
    )
    (net (code "75") (name "S4AA") (class "Default")
      (node (ref "R25") (pin "2") (pinfunction "2_2") (pintype "passive"))
      (node (ref "S101") (pin "A_A") (pinfunction "A_A_A_A") (pintype "bidirectional"))
    )
    (net (code "76") (name "S4B1") (class "Default")
      (node (ref "S101") (pin "B_1") (pinfunction "B_1_B_1") (pintype "bidirectional"))
      (node (ref "U4") (pin "26") (pinfunction "GPA5_26") (pintype "bidirectional"))
    )
    (net (code "77") (name "S4BA") (class "Default")
      (node (ref "R17") (pin "2") (pinfunction "2_2") (pintype "passive"))
      (node (ref "S101") (pin "B_A") (pinfunction "B_A_B_A") (pintype "bidirectional"))
    )
    (net (code "78") (name "S4C1") (class "Default")
      (node (ref "S101") (pin "C_1") (pinfunction "C_1_C_1") (pintype "bidirectional"))
      (node (ref "U4") (pin "27") (pinfunction "GPA6_27") (pintype "bidirectional"))
    )
    (net (code "79") (name "S4CA") (class "Default")
      (node (ref "R4") (pin "2") (pinfunction "2_2") (pintype "passive"))
      (node (ref "S101") (pin "C_A") (pinfunction "C_A_C_A") (pintype "bidirectional"))
    )
    (net (code "80") (name "SD_CARD_CS") (class "Default")
      (node (ref "J16") (pin "4") (pinfunction "4_4") (pintype "passive"))
      (node (ref "U2") (pin "1.6") (pinfunction "P1_6_1.6") (pintype "bidirectional"))
    )
    (net (code "81") (name "SPINDLE_DIRECTION_OUT") (class "Default")
      (node (ref "J6") (pin "2") (pinfunction "2_2") (pintype "passive"))
      (node (ref "U2") (pin "12.7") (pinfunction "P12_7_12.7") (pintype "bidirectional"))
    )
    (net (code "82") (name "SPINDLE_ENABLE_OUT") (class "Default")
      (node (ref "J6") (pin "1") (pinfunction "1_1") (pintype "passive"))
      (node (ref "U2") (pin "12.6") (pinfunction "P12_6_12.6") (pintype "bidirectional"))
    )
    (net (code "83") (name "SPINDLE_SPEED_OUT") (class "Default")
      (node (ref "J6") (pin "3") (pinfunction "3_3") (pintype "passive"))
      (node (ref "U2") (pin "2.7") (pinfunction "P2_7_2.7") (pintype "bidirectional"))
    )
    (net (code "84") (name "SPI_MISO") (class "Default")
      (node (ref "J16") (pin "6") (pinfunction "6_6") (pintype "passive"))
      (node (ref "U2") (pin "1.3") (pinfunction "P1_3_1.3") (pintype "bidirectional"))
    )
    (net (code "85") (name "SPI_MOSI") (class "Default")
      (node (ref "J16") (pin "3") (pinfunction "3_3") (pintype "passive"))
      (node (ref "U2") (pin "1.7") (pinfunction "P1_7_1.7") (pintype "bidirectional"))
    )
    (net (code "86") (name "SPI_SCK") (class "Default")
      (node (ref "J16") (pin "5") (pinfunction "5_5") (pintype "passive"))
      (node (ref "U2") (pin "1.5") (pinfunction "P1_5_1.5") (pintype "bidirectional"))
    )
    (net (code "87") (name "STEPPER_ENABLE_OUT") (class "Default")
      (node (ref "U2") (pin "0.4") (pinfunction "P0_4_0.4") (pintype "bidirectional"))
    )
    (net (code "88") (name "VIN") (class "Default")
      (node (ref "C1") (pin "+") (pinfunction "+_+") (pintype "passive"))
      (node (ref "J14") (pin "2") (pinfunction "2_2") (pintype "passive"))
      (node (ref "J14") (pin "3") (pinfunction "3_3") (pintype "passive"))
      (node (ref "R2") (pin "2") (pinfunction "2_2") (pintype "passive"))
      (node (ref "U1") (pin "1") (pinfunction "VIN_1") (pintype "bidirectional"))
    )
    (net (code "89") (name "VIN_SCALED_IN") (class "Default")
      (node (ref "C2") (pin "1") (pinfunction "1_1") (pintype "passive"))
      (node (ref "R1") (pin "2") (pinfunction "2_2") (pintype "passive"))
      (node (ref "R2") (pin "1") (pinfunction "1_1") (pintype "passive"))
      (node (ref "U2") (pin "2.0") (pinfunction "P2_0_2.0") (pintype "bidirectional"))
    )
    (net (code "90") (name "WHEEL_ENCODER_A_IN") (class "Default")
      (node (ref "J17") (pin "3") (pinfunction "3_3") (pintype "passive"))
      (node (ref "U2") (pin "12.2") (pinfunction "P12_2_12.2") (pintype "bidirectional"))
    )
    (net (code "91") (name "WHEEL_ENCODER_B_IN") (class "Default")
      (node (ref "J17") (pin "2") (pinfunction "2_2") (pintype "passive"))
      (node (ref "U2") (pin "12.3") (pinfunction "P12_3_12.3") (pintype "bidirectional"))
    )
    (net (code "92") (name "X_DIRECTION_OUT") (class "Default")
      (node (ref "J1") (pin "1") (pinfunction "1_1") (pintype "passive"))
      (node (ref "U2") (pin "3.1") (pinfunction "P3_1_3.1") (pintype "bidirectional"))
    )
    (net (code "93") (name "X_LIMIT_IN") (class "Default")
      (node (ref "J1") (pin "3") (pinfunction "3_3") (pintype "passive"))
      (node (ref "U2") (pin "3.4") (pinfunction "P3_4_3.4") (pintype "bidirectional"))
    )
    (net (code "94") (name "X_STEP_OUT") (class "Default")
      (node (ref "J1") (pin "2") (pinfunction "2_2") (pintype "passive"))
      (node (ref "U2") (pin "3.3") (pinfunction "P3_3_3.3") (pintype "bidirectional"))
    )
    (net (code "95") (name "Y_DIRECTION_OUT") (class "Default")
      (node (ref "J2") (pin "1") (pinfunction "1_1") (pintype "passive"))
      (node (ref "U2") (pin "3.5") (pinfunction "P3_5_3.5") (pintype "bidirectional"))
    )
    (net (code "96") (name "Y_LIMIT_IN") (class "Default")
      (node (ref "J2") (pin "3") (pinfunction "3_3") (pintype "passive"))
      (node (ref "U2") (pin "3.7") (pinfunction "P3_7_3.7") (pintype "bidirectional"))
    )
    (net (code "97") (name "Y_STEP_OUT") (class "Default")
      (node (ref "J2") (pin "2") (pinfunction "2_2") (pintype "passive"))
      (node (ref "U2") (pin "3.6") (pinfunction "P3_6_3.6") (pintype "bidirectional"))
    )
    (net (code "98") (name "Z_DIRECTION_OUT") (class "Default")
      (node (ref "J3") (pin "1") (pinfunction "1_1") (pintype "passive"))
      (node (ref "U2") (pin "15.5") (pinfunction "P15_5_15.5") (pintype "bidirectional"))
    )
    (net (code "99") (name "Z_DISPLAY_RX_IN") (class "Default")
      (node (ref "J19") (pin "2") (pinfunction "2_2") (pintype "passive"))
      (node (ref "U2") (pin "2.5") (pinfunction "P2_5_2.5") (pintype "bidirectional"))
    )
    (net (code "100") (name "Z_DISPLAY_TX_OUT") (class "Default")
      (node (ref "J19") (pin "1") (pinfunction "1_1") (pintype "passive"))
      (node (ref "U2") (pin "2.6") (pinfunction "P2_6_2.6") (pintype "bidirectional"))
    )
    (net (code "101") (name "Z_LIMIT_IN") (class "Default")
      (node (ref "J3") (pin "3") (pinfunction "3_3") (pintype "passive"))
      (node (ref "U2") (pin "0.1") (pinfunction "P0_1_0.1") (pintype "bidirectional"))
    )
    (net (code "102") (name "Z_STEP_OUT") (class "Default")
      (node (ref "J3") (pin "2") (pinfunction "2_2") (pintype "passive"))
      (node (ref "U2") (pin "0.0") (pinfunction "P0_0_0.0") (pintype "bidirectional"))
    )
    (net (code "103") (name "unconnected-(U2-P1_0-Pad1.0)") (class "Default")
      (node (ref "U2") (pin "1.0") (pinfunction "P1_0_1.0") (pintype "bidirectional"))
    )
    (net (code "104") (name "unconnected-(U2-P1_1-Pad1.1)") (class "Default")
      (node (ref "U2") (pin "1.1") (pinfunction "P1_1_1.1") (pintype "bidirectional"))
    )
    (net (code "105") (name "unconnected-(U2-PadVCCIO)") (class "Default")
      (node (ref "U2") (pin "VCCIO") (pinfunction "VCCIO_VCCIO") (pintype "bidirectional"))
    )
    (net (code "106") (name "unconnected-(U2-PadXRES)") (class "Default")
      (node (ref "U2") (pin "XRES") (pinfunction "XRES_XRES") (pintype "bidirectional"))
    )
    (net (code "107") (name "unconnected-(U3-INTB-Pad19)") (class "Default")
      (node (ref "U3") (pin "19") (pinfunction "INTB_19") (pintype "output"))
    )
    (net (code "108") (name "unconnected-(U4-INTB-Pad19)") (class "Default")
      (node (ref "U4") (pin "19") (pinfunction "INTB_19") (pintype "output"))
    )
    (net (code "109") (name "unconnected-(WEMOS1-Pad3V3)") (class "Default")
      (node (ref "WEMOS1") (pin "3V3") (pinfunction "3V3_3V3") (pintype "bidirectional"))
    )
    (net (code "110") (name "unconnected-(WEMOS1-PadA0)") (class "Default")
      (node (ref "WEMOS1") (pin "A0") (pinfunction "A0_A0") (pintype "bidirectional"))
    )
    (net (code "111") (name "unconnected-(WEMOS1-PadD0)") (class "Default")
      (node (ref "WEMOS1") (pin "D0") (pinfunction "D0_D0") (pintype "bidirectional"))
    )
    (net (code "112") (name "unconnected-(WEMOS1-PadD1)") (class "Default")
      (node (ref "WEMOS1") (pin "D1") (pinfunction "D1_D1") (pintype "bidirectional"))
    )
    (net (code "113") (name "unconnected-(WEMOS1-PadD2)") (class "Default")
      (node (ref "WEMOS1") (pin "D2") (pinfunction "D2_D2") (pintype "bidirectional"))
    )
    (net (code "114") (name "unconnected-(WEMOS1-PadD3)") (class "Default")
      (node (ref "WEMOS1") (pin "D3") (pinfunction "D3_D3") (pintype "bidirectional"))
    )
    (net (code "115") (name "unconnected-(WEMOS1-PadD4)") (class "Default")
      (node (ref "WEMOS1") (pin "D4") (pinfunction "D4_D4") (pintype "bidirectional"))
    )
    (net (code "116") (name "unconnected-(WEMOS1-PadD5)") (class "Default")
      (node (ref "WEMOS1") (pin "D5") (pinfunction "D5_D5") (pintype "bidirectional"))
    )
    (net (code "117") (name "unconnected-(WEMOS1-PadD6)") (class "Default")
      (node (ref "WEMOS1") (pin "D6") (pinfunction "D6_D6") (pintype "bidirectional"))
    )
    (net (code "118") (name "unconnected-(WEMOS1-PadD7)") (class "Default")
      (node (ref "WEMOS1") (pin "D7") (pinfunction "D7_D7") (pintype "bidirectional"))
    )
    (net (code "119") (name "unconnected-(WEMOS1-PadD8)") (class "Default")
      (node (ref "WEMOS1") (pin "D8") (pinfunction "D8_D8") (pintype "bidirectional"))
    )
    (net (code "120") (name "unconnected-(WEMOS1-PadRESET)") (class "Default")
      (node (ref "WEMOS1") (pin "RESET") (pinfunction "RESET_RESET") (pintype "bidirectional"))
    )
  )
)
